# console_schematic_switches.net
KiCad netlist of a schematic drawn in Altium Designer
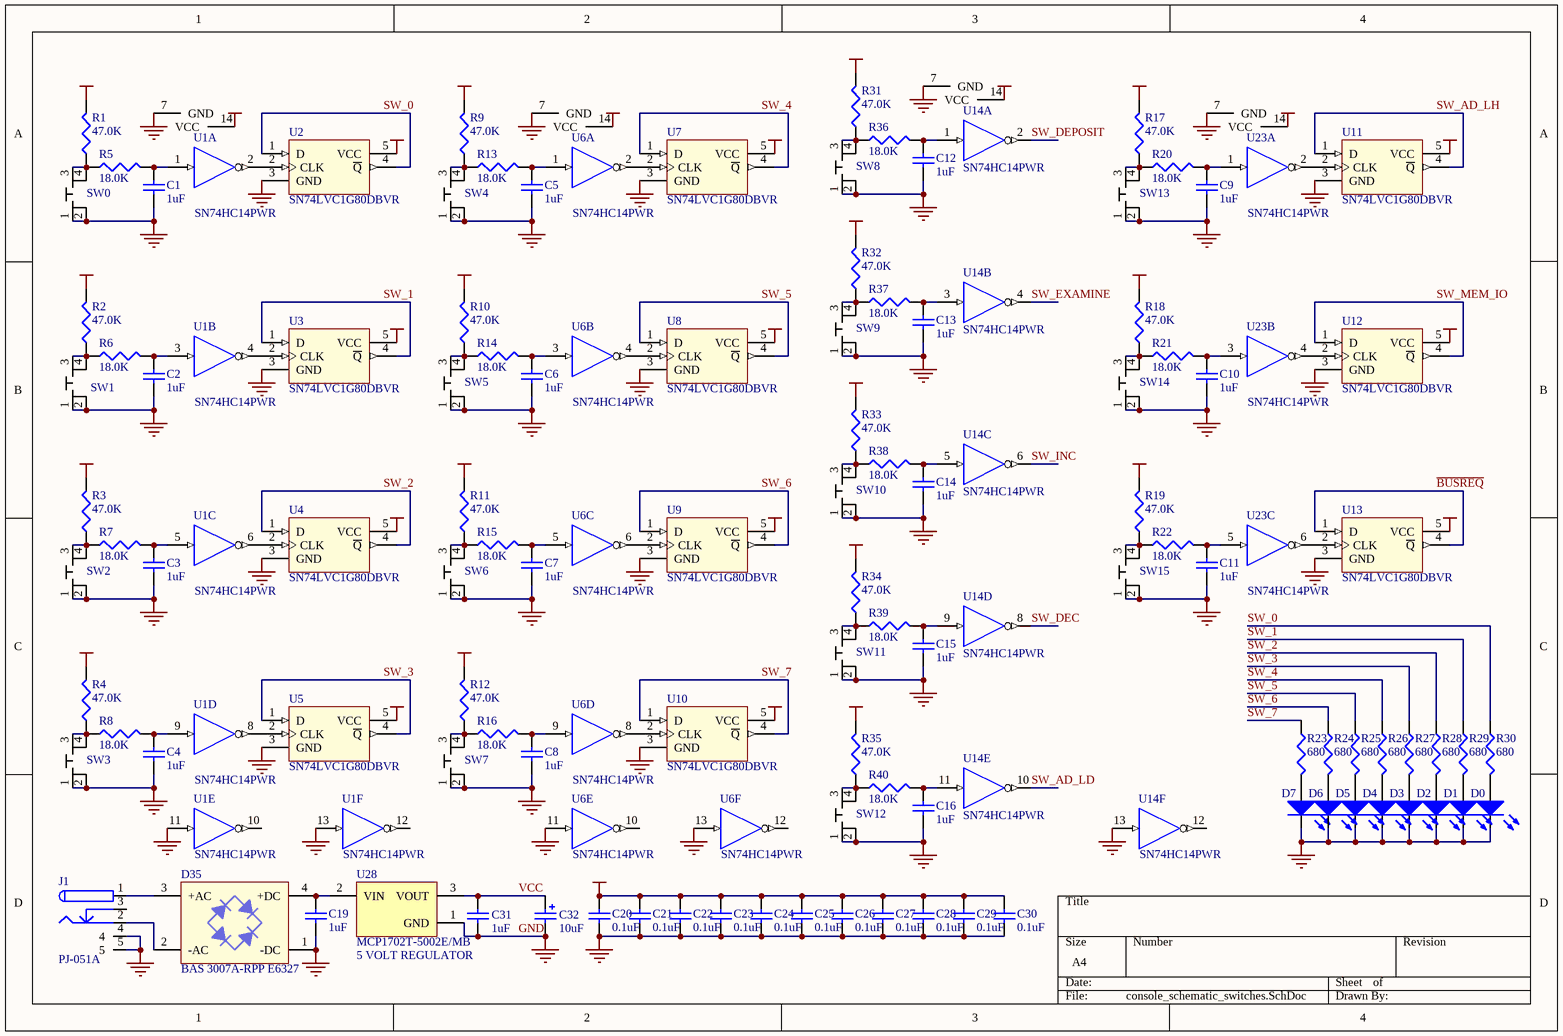
[diagram p0: console_schematic_switches.SchDoc]

(export (version "E")
  (design (tool "Eeschema 10.0.6"))
  (components
    (comp (ref "C1")
      (value "1uF")
      (footprint "smari_lib_pcb:0805")
      (description "CAP 1.0UF 16V CERAMIC X7R 0805")
      (libsource (lib "smari_lib_schematic") (part "C0805"))
    )
    (comp (ref "C2")
      (value "1uF")
      (footprint "smari_lib_pcb:0805")
      (description "CAP 1.0UF 16V CERAMIC X7R 0805")
      (libsource (lib "smari_lib_schematic") (part "C0805"))
    )
    (comp (ref "C3")
      (value "1uF")
      (footprint "smari_lib_pcb:0805")
      (description "CAP 1.0UF 16V CERAMIC X7R 0805")
      (libsource (lib "smari_lib_schematic") (part "C0805"))
    )
    (comp (ref "C4")
      (value "1uF")
      (footprint "smari_lib_pcb:0805")
      (description "CAP 1.0UF 16V CERAMIC X7R 0805")
      (libsource (lib "smari_lib_schematic") (part "C0805"))
    )
    (comp (ref "C5")
      (value "1uF")
      (footprint "smari_lib_pcb:0805")
      (description "CAP 1.0UF 16V CERAMIC X7R 0805")
      (libsource (lib "smari_lib_schematic") (part "C0805"))
    )
    (comp (ref "C6")
      (value "1uF")
      (footprint "smari_lib_pcb:0805")
      (description "CAP 1.0UF 16V CERAMIC X7R 0805")
      (libsource (lib "smari_lib_schematic") (part "C0805"))
    )
    (comp (ref "C7")
      (value "1uF")
      (footprint "smari_lib_pcb:0805")
      (description "CAP 1.0UF 16V CERAMIC X7R 0805")
      (libsource (lib "smari_lib_schematic") (part "C0805"))
    )
    (comp (ref "C8")
      (value "1uF")
      (footprint "smari_lib_pcb:0805")
      (description "CAP 1.0UF 16V CERAMIC X7R 0805")
      (libsource (lib "smari_lib_schematic") (part "C0805"))
    )
    (comp (ref "C9")
      (value "1uF")
      (footprint "smari_lib_pcb:0805")
      (description "CAP 1.0UF 16V CERAMIC X7R 0805")
      (libsource (lib "smari_lib_schematic") (part "C0805"))
    )
    (comp (ref "C10")
      (value "1uF")
      (footprint "smari_lib_pcb:0805")
      (description "CAP 1.0UF 16V CERAMIC X7R 0805")
      (libsource (lib "smari_lib_schematic") (part "C0805"))
    )
    (comp (ref "C11")
      (value "1uF")
      (footprint "smari_lib_pcb:0805")
      (description "CAP 1.0UF 16V CERAMIC X7R 0805")
      (libsource (lib "smari_lib_schematic") (part "C0805"))
    )
    (comp (ref "C12")
      (value "1uF")
      (footprint "smari_lib_pcb:0805")
      (description "CAP 1.0UF 16V CERAMIC X7R 0805")
      (libsource (lib "smari_lib_schematic") (part "C0805"))
    )
    (comp (ref "C13")
      (value "1uF")
      (footprint "smari_lib_pcb:0805")
      (description "CAP 1.0UF 16V CERAMIC X7R 0805")
      (libsource (lib "smari_lib_schematic") (part "C0805"))
    )
    (comp (ref "C14")
      (value "1uF")
      (footprint "smari_lib_pcb:0805")
      (description "CAP 1.0UF 16V CERAMIC X7R 0805")
      (libsource (lib "smari_lib_schematic") (part "C0805"))
    )
    (comp (ref "C15")
      (value "1uF")
      (footprint "smari_lib_pcb:0805")
      (description "CAP 1.0UF 16V CERAMIC X7R 0805")
      (libsource (lib "smari_lib_schematic") (part "C0805"))
    )
    (comp (ref "C16")
      (value "1uF")
      (footprint "smari_lib_pcb:0805")
      (description "CAP 1.0UF 16V CERAMIC X7R 0805")
      (libsource (lib "smari_lib_schematic") (part "C0805"))
    )
    (comp (ref "C19")
      (value "1uF")
      (footprint "smari_lib_pcb:0805")
      (description "CAP 1.0UF 16V CERAMIC X7R 0805")
      (libsource (lib "smari_lib_schematic") (part "C0805"))
    )
    (comp (ref "C20")
      (value "0.1uF")
      (footprint "smari_lib_pcb:0603")
      (description "CAP .10UF 16V CERAMIC X7R 0603")
      (libsource (lib "smari_lib_schematic") (part "C0603"))
    )
    (comp (ref "C21")
      (value "0.1uF")
      (footprint "smari_lib_pcb:0603")
      (description "CAP .10UF 16V CERAMIC X7R 0603")
      (libsource (lib "smari_lib_schematic") (part "C0603"))
    )
    (comp (ref "C22")
      (value "0.1uF")
      (footprint "smari_lib_pcb:0603")
      (description "CAP .10UF 16V CERAMIC X7R 0603")
      (libsource (lib "smari_lib_schematic") (part "C0603"))
    )
    (comp (ref "C23")
      (value "0.1uF")
      (footprint "smari_lib_pcb:0603")
      (description "CAP .10UF 16V CERAMIC X7R 0603")
      (libsource (lib "smari_lib_schematic") (part "C0603"))
    )
    (comp (ref "C24")
      (value "0.1uF")
      (footprint "smari_lib_pcb:0603")
      (description "CAP .10UF 16V CERAMIC X7R 0603")
      (libsource (lib "smari_lib_schematic") (part "C0603"))
    )
    (comp (ref "C25")
      (value "0.1uF")
      (footprint "smari_lib_pcb:0603")
      (description "CAP .10UF 16V CERAMIC X7R 0603")
      (libsource (lib "smari_lib_schematic") (part "C0603"))
    )
    (comp (ref "C26")
      (value "0.1uF")
      (footprint "smari_lib_pcb:0603")
      (description "CAP .10UF 16V CERAMIC X7R 0603")
      (libsource (lib "smari_lib_schematic") (part "C0603"))
    )
    (comp (ref "C27")
      (value "0.1uF")
      (footprint "smari_lib_pcb:0603")
      (description "CAP .10UF 16V CERAMIC X7R 0603")
      (libsource (lib "smari_lib_schematic") (part "C0603"))
    )
    (comp (ref "C28")
      (value "0.1uF")
      (footprint "smari_lib_pcb:0603")
      (description "CAP .10UF 16V CERAMIC X7R 0603")
      (libsource (lib "smari_lib_schematic") (part "C0603"))
    )
    (comp (ref "C29")
      (value "0.1uF")
      (footprint "smari_lib_pcb:0603")
      (description "CAP .10UF 16V CERAMIC X7R 0603")
      (libsource (lib "smari_lib_schematic") (part "C0603"))
    )
    (comp (ref "C30")
      (value "0.1uF")
      (footprint "smari_lib_pcb:0603")
      (description "CAP .10UF 16V CERAMIC X7R 0603")
      (libsource (lib "smari_lib_schematic") (part "C0603"))
    )
    (comp (ref "C31")
      (value "1uF")
      (footprint "smari_lib_pcb:0805")
      (description "CAP 1.0UF 16V CERAMIC X7R 0805")
      (libsource (lib "smari_lib_schematic") (part "C0805"))
    )
    (comp (ref "C32")
      (value "10uF")
      (footprint "smari_lib_pcb:1206_A")
      (description "CAPACITOR TANT 10UF 10V 10% SMD")
      (libsource (lib "smari_lib_schematic") (part "T491A"))
    )
    (comp (ref "D0")
      (value "LTST-C190KRKT")
      (footprint "smari_lib_pcb:APG1608")
      (description "LED SUPER RED CLEAR 0603 SMD")
      (libsource (lib "smari_lib_schematic") (part "LTST-C190KRKT"))
    )
    (comp (ref "D1")
      (value "LTST-C190KRKT")
      (footprint "smari_lib_pcb:APG1608")
      (description "LED SUPER RED CLEAR 0603 SMD")
      (libsource (lib "smari_lib_schematic") (part "LTST-C190KRKT"))
    )
    (comp (ref "D2")
      (value "LTST-C190KRKT")
      (footprint "smari_lib_pcb:APG1608")
      (description "LED SUPER RED CLEAR 0603 SMD")
      (libsource (lib "smari_lib_schematic") (part "LTST-C190KRKT"))
    )
    (comp (ref "D3")
      (value "LTST-C190KRKT")
      (footprint "smari_lib_pcb:APG1608")
      (description "LED SUPER RED CLEAR 0603 SMD")
      (libsource (lib "smari_lib_schematic") (part "LTST-C190KRKT"))
    )
    (comp (ref "D4")
      (value "LTST-C190KRKT")
      (footprint "smari_lib_pcb:APG1608")
      (description "LED SUPER RED CLEAR 0603 SMD")
      (libsource (lib "smari_lib_schematic") (part "LTST-C190KRKT"))
    )
    (comp (ref "D5")
      (value "LTST-C190KRKT")
      (footprint "smari_lib_pcb:APG1608")
      (description "LED SUPER RED CLEAR 0603 SMD")
      (libsource (lib "smari_lib_schematic") (part "LTST-C190KRKT"))
    )
    (comp (ref "D6")
      (value "LTST-C190KRKT")
      (footprint "smari_lib_pcb:APG1608")
      (description "LED SUPER RED CLEAR 0603 SMD")
      (libsource (lib "smari_lib_schematic") (part "LTST-C190KRKT"))
    )
    (comp (ref "D7")
      (value "LTST-C190KRKT")
      (footprint "smari_lib_pcb:APG1608")
      (description "LED SUPER RED CLEAR 0603 SMD")
      (libsource (lib "smari_lib_schematic") (part "LTST-C190KRKT"))
    )
    (comp (ref "D35")
      (value "BAS 3007A-RPP E6327")
      (footprint "smari_lib_pcb:SOT143")
      (description "DIODE SCHOTTKY 30V 900MA SOT143")
      (libsource (lib "smari_lib_schematic") (part "BAS 3007A-RPP E6327"))
    )
    (comp (ref "J1")
      (value "PJ-051A")
      (footprint "smari_lib_pcb:PJ-051A")
      (description "CON PWR JCK 2.0 X 6.0MM W/SHLD")
      (libsource (lib "smari_lib_schematic") (part "PJ-051A"))
    )
    (comp (ref "R1")
      (value "47.0K")
      (footprint "smari_lib_pcb:0603")
      (description "RES 47.0K OHM 1/10W 1% 0603 SMD")
      (libsource (lib "smari_lib_schematic") (part "MCR03EZPFX"))
    )
    (comp (ref "R2")
      (value "47.0K")
      (footprint "smari_lib_pcb:0603")
      (description "RES 47.0K OHM 1/10W 1% 0603 SMD")
      (libsource (lib "smari_lib_schematic") (part "MCR03EZPFX"))
    )
    (comp (ref "R3")
      (value "47.0K")
      (footprint "smari_lib_pcb:0603")
      (description "RES 47.0K OHM 1/10W 1% 0603 SMD")
      (libsource (lib "smari_lib_schematic") (part "MCR03EZPFX"))
    )
    (comp (ref "R4")
      (value "47.0K")
      (footprint "smari_lib_pcb:0603")
      (description "RES 47.0K OHM 1/10W 1% 0603 SMD")
      (libsource (lib "smari_lib_schematic") (part "MCR03EZPFX"))
    )
    (comp (ref "R5")
      (value "18.0K")
      (footprint "smari_lib_pcb:0603")
      (description "RES 18.0K OHM 1/10W 1% 0603 SMD")
      (libsource (lib "smari_lib_schematic") (part "MCR03EZPFX"))
    )
    (comp (ref "R6")
      (value "18.0K")
      (footprint "smari_lib_pcb:0603")
      (description "RES 18.0K OHM 1/10W 1% 0603 SMD")
      (libsource (lib "smari_lib_schematic") (part "MCR03EZPFX"))
    )
    (comp (ref "R7")
      (value "18.0K")
      (footprint "smari_lib_pcb:0603")
      (description "RES 18.0K OHM 1/10W 1% 0603 SMD")
      (libsource (lib "smari_lib_schematic") (part "MCR03EZPFX"))
    )
    (comp (ref "R8")
      (value "18.0K")
      (footprint "smari_lib_pcb:0603")
      (description "RES 18.0K OHM 1/10W 1% 0603 SMD")
      (libsource (lib "smari_lib_schematic") (part "MCR03EZPFX"))
    )
    (comp (ref "R9")
      (value "47.0K")
      (footprint "smari_lib_pcb:0603")
      (description "RES 47.0K OHM 1/10W 1% 0603 SMD")
      (libsource (lib "smari_lib_schematic") (part "MCR03EZPFX"))
    )
    (comp (ref "R10")
      (value "47.0K")
      (footprint "smari_lib_pcb:0603")
      (description "RES 47.0K OHM 1/10W 1% 0603 SMD")
      (libsource (lib "smari_lib_schematic") (part "MCR03EZPFX"))
    )
    (comp (ref "R11")
      (value "47.0K")
      (footprint "smari_lib_pcb:0603")
      (description "RES 47.0K OHM 1/10W 1% 0603 SMD")
      (libsource (lib "smari_lib_schematic") (part "MCR03EZPFX"))
    )
    (comp (ref "R12")
      (value "47.0K")
      (footprint "smari_lib_pcb:0603")
      (description "RES 47.0K OHM 1/10W 1% 0603 SMD")
      (libsource (lib "smari_lib_schematic") (part "MCR03EZPFX"))
    )
    (comp (ref "R13")
      (value "18.0K")
      (footprint "smari_lib_pcb:0603")
      (description "RES 18.0K OHM 1/10W 1% 0603 SMD")
      (libsource (lib "smari_lib_schematic") (part "MCR03EZPFX"))
    )
    (comp (ref "R14")
      (value "18.0K")
      (footprint "smari_lib_pcb:0603")
      (description "RES 18.0K OHM 1/10W 1% 0603 SMD")
      (libsource (lib "smari_lib_schematic") (part "MCR03EZPFX"))
    )
    (comp (ref "R15")
      (value "18.0K")
      (footprint "smari_lib_pcb:0603")
      (description "RES 18.0K OHM 1/10W 1% 0603 SMD")
      (libsource (lib "smari_lib_schematic") (part "MCR03EZPFX"))
    )
    (comp (ref "R16")
      (value "18.0K")
      (footprint "smari_lib_pcb:0603")
      (description "RES 18.0K OHM 1/10W 1% 0603 SMD")
      (libsource (lib "smari_lib_schematic") (part "MCR03EZPFX"))
    )
    (comp (ref "R17")
      (value "47.0K")
      (footprint "smari_lib_pcb:0603")
      (description "RES 47.0K OHM 1/10W 1% 0603 SMD")
      (libsource (lib "smari_lib_schematic") (part "MCR03EZPFX"))
    )
    (comp (ref "R18")
      (value "47.0K")
      (footprint "smari_lib_pcb:0603")
      (description "RES 47.0K OHM 1/10W 1% 0603 SMD")
      (libsource (lib "smari_lib_schematic") (part "MCR03EZPFX"))
    )
    (comp (ref "R19")
      (value "47.0K")
      (footprint "smari_lib_pcb:0603")
      (description "RES 47.0K OHM 1/10W 1% 0603 SMD")
      (libsource (lib "smari_lib_schematic") (part "MCR03EZPFX"))
    )
    (comp (ref "R20")
      (value "18.0K")
      (footprint "smari_lib_pcb:0603")
      (description "RES 18.0K OHM 1/10W 1% 0603 SMD")
      (libsource (lib "smari_lib_schematic") (part "MCR03EZPFX"))
    )
    (comp (ref "R21")
      (value "18.0K")
      (footprint "smari_lib_pcb:0603")
      (description "RES 18.0K OHM 1/10W 1% 0603 SMD")
      (libsource (lib "smari_lib_schematic") (part "MCR03EZPFX"))
    )
    (comp (ref "R22")
      (value "18.0K")
      (footprint "smari_lib_pcb:0603")
      (description "RES 18.0K OHM 1/10W 1% 0603 SMD")
      (libsource (lib "smari_lib_schematic") (part "MCR03EZPFX"))
    )
    (comp (ref "R23")
      (value "680")
      (footprint "smari_lib_pcb:0603")
      (description "RES 680 OHM 1/10W 1% 0603 SMD")
      (libsource (lib "smari_lib_schematic") (part "MCR03EZPFX"))
    )
    (comp (ref "R24")
      (value "680")
      (footprint "smari_lib_pcb:0603")
      (description "RES 680 OHM 1/10W 1% 0603 SMD")
      (libsource (lib "smari_lib_schematic") (part "MCR03EZPFX"))
    )
    (comp (ref "R25")
      (value "680")
      (footprint "smari_lib_pcb:0603")
      (description "RES 680 OHM 1/10W 1% 0603 SMD")
      (libsource (lib "smari_lib_schematic") (part "MCR03EZPFX"))
    )
    (comp (ref "R26")
      (value "680")
      (footprint "smari_lib_pcb:0603")
      (description "RES 680 OHM 1/10W 1% 0603 SMD")
      (libsource (lib "smari_lib_schematic") (part "MCR03EZPFX"))
    )
    (comp (ref "R27")
      (value "680")
      (footprint "smari_lib_pcb:0603")
      (description "RES 680 OHM 1/10W 1% 0603 SMD")
      (libsource (lib "smari_lib_schematic") (part "MCR03EZPFX"))
    )
    (comp (ref "R28")
      (value "680")
      (footprint "smari_lib_pcb:0603")
      (description "RES 680 OHM 1/10W 1% 0603 SMD")
      (libsource (lib "smari_lib_schematic") (part "MCR03EZPFX"))
    )
    (comp (ref "R29")
      (value "680")
      (footprint "smari_lib_pcb:0603")
      (description "RES 680 OHM 1/10W 1% 0603 SMD")
      (libsource (lib "smari_lib_schematic") (part "MCR03EZPFX"))
    )
    (comp (ref "R30")
      (value "680")
      (footprint "smari_lib_pcb:0603")
      (description "RES 680 OHM 1/10W 1% 0603 SMD")
      (libsource (lib "smari_lib_schematic") (part "MCR03EZPFX"))
    )
    (comp (ref "R31")
      (value "47.0K")
      (footprint "smari_lib_pcb:0603")
      (description "RES 47.0K OHM 1/10W 1% 0603 SMD")
      (libsource (lib "smari_lib_schematic") (part "MCR03EZPFX"))
    )
    (comp (ref "R32")
      (value "47.0K")
      (footprint "smari_lib_pcb:0603")
      (description "RES 47.0K OHM 1/10W 1% 0603 SMD")
      (libsource (lib "smari_lib_schematic") (part "MCR03EZPFX"))
    )
    (comp (ref "R33")
      (value "47.0K")
      (footprint "smari_lib_pcb:0603")
      (description "RES 47.0K OHM 1/10W 1% 0603 SMD")
      (libsource (lib "smari_lib_schematic") (part "MCR03EZPFX"))
    )
    (comp (ref "R34")
      (value "47.0K")
      (footprint "smari_lib_pcb:0603")
      (description "RES 47.0K OHM 1/10W 1% 0603 SMD")
      (libsource (lib "smari_lib_schematic") (part "MCR03EZPFX"))
    )
    (comp (ref "R35")
      (value "47.0K")
      (footprint "smari_lib_pcb:0603")
      (description "RES 47.0K OHM 1/10W 1% 0603 SMD")
      (libsource (lib "smari_lib_schematic") (part "MCR03EZPFX"))
    )
    (comp (ref "R36")
      (value "18.0K")
      (footprint "smari_lib_pcb:0603")
      (description "RES 18.0K OHM 1/10W 1% 0603 SMD")
      (libsource (lib "smari_lib_schematic") (part "MCR03EZPFX"))
    )
    (comp (ref "R37")
      (value "18.0K")
      (footprint "smari_lib_pcb:0603")
      (description "RES 18.0K OHM 1/10W 1% 0603 SMD")
      (libsource (lib "smari_lib_schematic") (part "MCR03EZPFX"))
    )
    (comp (ref "R38")
      (value "18.0K")
      (footprint "smari_lib_pcb:0603")
      (description "RES 18.0K OHM 1/10W 1% 0603 SMD")
      (libsource (lib "smari_lib_schematic") (part "MCR03EZPFX"))
    )
    (comp (ref "R39")
      (value "18.0K")
      (footprint "smari_lib_pcb:0603")
      (description "RES 18.0K OHM 1/10W 1% 0603 SMD")
      (libsource (lib "smari_lib_schematic") (part "MCR03EZPFX"))
    )
    (comp (ref "R40")
      (value "18.0K")
      (footprint "smari_lib_pcb:0603")
      (description "RES 18.0K OHM 1/10W 1% 0603 SMD")
      (libsource (lib "smari_lib_schematic") (part "MCR03EZPFX"))
    )
    (comp (ref "SW0")
      (value "PTS645SM43SMTR LFS")
      (footprint "smari_lib_pcb:PTS645SM43SMTR LFS")
      (description "SWITCH TACT 6MM 160GF H=4.3MM")
      (libsource (lib "smari_lib_schematic") (part "PTS645SM43SMTR LFS"))
    )
    (comp (ref "SW1")
      (value "PTS645SM43SMTR LFS")
      (footprint "smari_lib_pcb:PTS645SM43SMTR LFS")
      (description "SWITCH TACT 6MM 160GF H=4.3MM")
      (libsource (lib "smari_lib_schematic") (part "PTS645SM43SMTR LFS"))
    )
    (comp (ref "SW2")
      (value "PTS645SM43SMTR LFS")
      (footprint "smari_lib_pcb:PTS645SM43SMTR LFS")
      (description "SWITCH TACT 6MM 160GF H=4.3MM")
      (libsource (lib "smari_lib_schematic") (part "PTS645SM43SMTR LFS"))
    )
    (comp (ref "SW3")
      (value "PTS645SM43SMTR LFS")
      (footprint "smari_lib_pcb:PTS645SM43SMTR LFS")
      (description "SWITCH TACT 6MM 160GF H=4.3MM")
      (libsource (lib "smari_lib_schematic") (part "PTS645SM43SMTR LFS"))
    )
    (comp (ref "SW4")
      (value "PTS645SM43SMTR LFS")
      (footprint "smari_lib_pcb:PTS645SM43SMTR LFS")
      (description "SWITCH TACT 6MM 160GF H=4.3MM")
      (libsource (lib "smari_lib_schematic") (part "PTS645SM43SMTR LFS"))
    )
    (comp (ref "SW5")
      (value "PTS645SM43SMTR LFS")
      (footprint "smari_lib_pcb:PTS645SM43SMTR LFS")
      (description "SWITCH TACT 6MM 160GF H=4.3MM")
      (libsource (lib "smari_lib_schematic") (part "PTS645SM43SMTR LFS"))
    )
    (comp (ref "SW6")
      (value "PTS645SM43SMTR LFS")
      (footprint "smari_lib_pcb:PTS645SM43SMTR LFS")
      (description "SWITCH TACT 6MM 160GF H=4.3MM")
      (libsource (lib "smari_lib_schematic") (part "PTS645SM43SMTR LFS"))
    )
    (comp (ref "SW7")
      (value "PTS645SM43SMTR LFS")
      (footprint "smari_lib_pcb:PTS645SM43SMTR LFS")
      (description "SWITCH TACT 6MM 160GF H=4.3MM")
      (libsource (lib "smari_lib_schematic") (part "PTS645SM43SMTR LFS"))
    )
    (comp (ref "SW8")
      (value "PTS645SM43SMTR LFS")
      (footprint "smari_lib_pcb:PTS645SM43SMTR LFS")
      (description "SWITCH TACT 6MM 160GF H=4.3MM")
      (libsource (lib "smari_lib_schematic") (part "PTS645SM43SMTR LFS"))
    )
    (comp (ref "SW9")
      (value "PTS645SM43SMTR LFS")
      (footprint "smari_lib_pcb:PTS645SM43SMTR LFS")
      (description "SWITCH TACT 6MM 160GF H=4.3MM")
      (libsource (lib "smari_lib_schematic") (part "PTS645SM43SMTR LFS"))
    )
    (comp (ref "SW10")
      (value "PTS645SM43SMTR LFS")
      (footprint "smari_lib_pcb:PTS645SM43SMTR LFS")
      (description "SWITCH TACT 6MM 160GF H=4.3MM")
      (libsource (lib "smari_lib_schematic") (part "PTS645SM43SMTR LFS"))
    )
    (comp (ref "SW11")
      (value "PTS645SM43SMTR LFS")
      (footprint "smari_lib_pcb:PTS645SM43SMTR LFS")
      (description "SWITCH TACT 6MM 160GF H=4.3MM")
      (libsource (lib "smari_lib_schematic") (part "PTS645SM43SMTR LFS"))
    )
    (comp (ref "SW12")
      (value "PTS645SM43SMTR LFS")
      (footprint "smari_lib_pcb:PTS645SM43SMTR LFS")
      (description "SWITCH TACT 6MM 160GF H=4.3MM")
      (libsource (lib "smari_lib_schematic") (part "PTS645SM43SMTR LFS"))
    )
    (comp (ref "SW13")
      (value "PTS645SM43SMTR LFS")
      (footprint "smari_lib_pcb:PTS645SM43SMTR LFS")
      (description "SWITCH TACT 6MM 160GF H=4.3MM")
      (libsource (lib "smari_lib_schematic") (part "PTS645SM43SMTR LFS"))
    )
    (comp (ref "SW14")
      (value "PTS645SM43SMTR LFS")
      (footprint "smari_lib_pcb:PTS645SM43SMTR LFS")
      (description "SWITCH TACT 6MM 160GF H=4.3MM")
      (libsource (lib "smari_lib_schematic") (part "PTS645SM43SMTR LFS"))
    )
    (comp (ref "SW15")
      (value "PTS645SM43SMTR LFS")
      (footprint "smari_lib_pcb:PTS645SM43SMTR LFS")
      (description "SWITCH TACT 6MM 160GF H=4.3MM")
      (libsource (lib "smari_lib_schematic") (part "PTS645SM43SMTR LFS"))
    )
    (comp (ref "U1")
      (value "SN74HC14PWR")
      (footprint "smari_lib_pcb:PW014")
      (description "IC HEX SCHMITT-TRIG INV 14-TSSOP")
      (libsource (lib "smari_lib_schematic") (part "SN74HC14PWR"))
    )
    (comp (ref "U2")
      (value "SN74LVC1G80DBVR")
      (footprint "smari_lib_pcb:SOT-23-5 DBV R-PDSO-G5")
      (description "IC POSITIVE D-TYPE F-F SOT-23-5")
      (libsource (lib "smari_lib_schematic") (part "SN74LVC1G80DBVR"))
    )
    (comp (ref "U3")
      (value "SN74LVC1G80DBVR")
      (footprint "smari_lib_pcb:SOT-23-5 DBV R-PDSO-G5")
      (description "IC POSITIVE D-TYPE F-F SOT-23-5")
      (libsource (lib "smari_lib_schematic") (part "SN74LVC1G80DBVR"))
    )
    (comp (ref "U4")
      (value "SN74LVC1G80DBVR")
      (footprint "smari_lib_pcb:SOT-23-5 DBV R-PDSO-G5")
      (description "IC POSITIVE D-TYPE F-F SOT-23-5")
      (libsource (lib "smari_lib_schematic") (part "SN74LVC1G80DBVR"))
    )
    (comp (ref "U5")
      (value "SN74LVC1G80DBVR")
      (footprint "smari_lib_pcb:SOT-23-5 DBV R-PDSO-G5")
      (description "IC POSITIVE D-TYPE F-F SOT-23-5")
      (libsource (lib "smari_lib_schematic") (part "SN74LVC1G80DBVR"))
    )
    (comp (ref "U6")
      (value "SN74HC14PWR")
      (footprint "smari_lib_pcb:PW014")
      (description "IC HEX SCHMITT-TRIG INV 14-TSSOP")
      (libsource (lib "smari_lib_schematic") (part "SN74HC14PWR"))
    )
    (comp (ref "U7")
      (value "SN74LVC1G80DBVR")
      (footprint "smari_lib_pcb:SOT-23-5 DBV R-PDSO-G5")
      (description "IC POSITIVE D-TYPE F-F SOT-23-5")
      (libsource (lib "smari_lib_schematic") (part "SN74LVC1G80DBVR"))
    )
    (comp (ref "U8")
      (value "SN74LVC1G80DBVR")
      (footprint "smari_lib_pcb:SOT-23-5 DBV R-PDSO-G5")
      (description "IC POSITIVE D-TYPE F-F SOT-23-5")
      (libsource (lib "smari_lib_schematic") (part "SN74LVC1G80DBVR"))
    )
    (comp (ref "U9")
      (value "SN74LVC1G80DBVR")
      (footprint "smari_lib_pcb:SOT-23-5 DBV R-PDSO-G5")
      (description "IC POSITIVE D-TYPE F-F SOT-23-5")
      (libsource (lib "smari_lib_schematic") (part "SN74LVC1G80DBVR"))
    )
    (comp (ref "U10")
      (value "SN74LVC1G80DBVR")
      (footprint "smari_lib_pcb:SOT-23-5 DBV R-PDSO-G5")
      (description "IC POSITIVE D-TYPE F-F SOT-23-5")
      (libsource (lib "smari_lib_schematic") (part "SN74LVC1G80DBVR"))
    )
    (comp (ref "U11")
      (value "SN74LVC1G80DBVR")
      (footprint "smari_lib_pcb:SOT-23-5 DBV R-PDSO-G5")
      (description "IC POSITIVE D-TYPE F-F SOT-23-5")
      (libsource (lib "smari_lib_schematic") (part "SN74LVC1G80DBVR"))
    )
    (comp (ref "U12")
      (value "SN74LVC1G80DBVR")
      (footprint "smari_lib_pcb:SOT-23-5 DBV R-PDSO-G5")
      (description "IC POSITIVE D-TYPE F-F SOT-23-5")
      (libsource (lib "smari_lib_schematic") (part "SN74LVC1G80DBVR"))
    )
    (comp (ref "U13")
      (value "SN74LVC1G80DBVR")
      (footprint "smari_lib_pcb:SOT-23-5 DBV R-PDSO-G5")
      (description "IC POSITIVE D-TYPE F-F SOT-23-5")
      (libsource (lib "smari_lib_schematic") (part "SN74LVC1G80DBVR"))
    )
    (comp (ref "U14")
      (value "SN74HC14PWR")
      (footprint "smari_lib_pcb:PW014")
      (description "IC HEX SCHMITT-TRIG INV 14-TSSOP")
      (libsource (lib "") (part "SN74HC14PWR_2"))
    )
    (comp (ref "U23")
      (value "SN74HC14PWR")
      (footprint "smari_lib_pcb:PW014")
      (description "IC HEX SCHMITT-TRIG INV 14-TSSOP")
      (libsource (lib "smari_lib_schematic") (part "SN74HC14PWR"))
    )
    (comp (ref "U28")
      (value "MCP1702T-5002E/MB")
      (footprint "smari_lib_pcb:SOT-89")
      (description "IC REG LDO 5V 250MA SOT-89-3")
      (fields (field (name "NOTES") "5 VOLT REGULATOR"))
      (libsource (lib "smari_lib_schematic") (part "MCP1702T-5002E/MB"))
    )
  )
  (nets
    (net (code "1") (name "/SW_0") (class "Default")
      (node (ref "R30") (pin "1") (pinfunction "1_1") (pintype "passive"))
      (node (ref "U2") (pin "1") (pinfunction "D_1") (pintype "input"))
      (node (ref "U2") (pin "4") (pinfunction "~{Q}_4") (pintype "output"))
    )
    (net (code "2") (name "/SW_1") (class "Default")
      (node (ref "R29") (pin "1") (pinfunction "1_1") (pintype "passive"))
      (node (ref "U3") (pin "1") (pinfunction "D_1") (pintype "input"))
      (node (ref "U3") (pin "4") (pinfunction "~{Q}_4") (pintype "output"))
    )
    (net (code "3") (name "/SW_2") (class "Default")
      (node (ref "R28") (pin "1") (pinfunction "1_1") (pintype "passive"))
      (node (ref "U4") (pin "1") (pinfunction "D_1") (pintype "input"))
      (node (ref "U4") (pin "4") (pinfunction "~{Q}_4") (pintype "output"))
    )
    (net (code "4") (name "/SW_3") (class "Default")
      (node (ref "R27") (pin "1") (pinfunction "1_1") (pintype "passive"))
      (node (ref "U5") (pin "1") (pinfunction "D_1") (pintype "input"))
      (node (ref "U5") (pin "4") (pinfunction "~{Q}_4") (pintype "output"))
    )
    (net (code "5") (name "/SW_4") (class "Default")
      (node (ref "R26") (pin "1") (pinfunction "1_1") (pintype "passive"))
      (node (ref "U7") (pin "1") (pinfunction "D_1") (pintype "input"))
      (node (ref "U7") (pin "4") (pinfunction "~{Q}_4") (pintype "output"))
    )
    (net (code "6") (name "/SW_5") (class "Default")
      (node (ref "R25") (pin "1") (pinfunction "1_1") (pintype "passive"))
      (node (ref "U8") (pin "1") (pinfunction "D_1") (pintype "input"))
      (node (ref "U8") (pin "4") (pinfunction "~{Q}_4") (pintype "output"))
    )
    (net (code "7") (name "/SW_6") (class "Default")
      (node (ref "R24") (pin "1") (pinfunction "1_1") (pintype "passive"))
      (node (ref "U9") (pin "1") (pinfunction "D_1") (pintype "input"))
      (node (ref "U9") (pin "4") (pinfunction "~{Q}_4") (pintype "output"))
    )
    (net (code "8") (name "/SW_7") (class "Default")
      (node (ref "R23") (pin "1") (pinfunction "1_1") (pintype "passive"))
      (node (ref "U10") (pin "1") (pinfunction "D_1") (pintype "input"))
      (node (ref "U10") (pin "4") (pinfunction "~{Q}_4") (pintype "output"))
    )
    (net (code "9") (name "/SW_AD_LD") (class "Default")
      (node (ref "U14") (pin "10") (pinfunction "Y_10") (pintype "output"))
    )
    (net (code "10") (name "/SW_AD_LH") (class "Default")
      (node (ref "U11") (pin "1") (pinfunction "D_1") (pintype "input"))
      (node (ref "U11") (pin "4") (pinfunction "~{Q}_4") (pintype "output"))
    )
    (net (code "11") (name "/SW_DEC") (class "Default")
      (node (ref "U14") (pin "8") (pinfunction "Y_8") (pintype "output"))
    )
    (net (code "12") (name "/SW_DEPOSIT") (class "Default")
      (node (ref "U14") (pin "2") (pinfunction "Y_2") (pintype "output"))
    )
    (net (code "13") (name "/SW_EXAMINE") (class "Default")
      (node (ref "U14") (pin "4") (pinfunction "Y_4") (pintype "output"))
    )
    (net (code "14") (name "/SW_INC") (class "Default")
      (node (ref "U14") (pin "6") (pinfunction "Y_6") (pintype "output"))
    )
    (net (code "15") (name "/SW_MEM_IO") (class "Default")
      (node (ref "U12") (pin "1") (pinfunction "D_1") (pintype "input"))
      (node (ref "U12") (pin "4") (pinfunction "~{Q}_4") (pintype "output"))
    )
    (net (code "16") (name "/~{BUSREQ}") (class "Default")
      (node (ref "U13") (pin "1") (pinfunction "D_1") (pintype "input"))
      (node (ref "U13") (pin "4") (pinfunction "~{Q}_4") (pintype "output"))
    )
    (net (code "17") (name "GND") (class "Default")
      (node (ref "C1") (pin "1") (pinfunction "1_1") (pintype "passive"))
      (node (ref "C10") (pin "1") (pinfunction "1_1") (pintype "passive"))
      (node (ref "C11") (pin "1") (pinfunction "1_1") (pintype "passive"))
      (node (ref "C12") (pin "1") (pinfunction "1_1") (pintype "passive"))
      (node (ref "C13") (pin "1") (pinfunction "1_1") (pintype "passive"))
      (node (ref "C14") (pin "1") (pinfunction "1_1") (pintype "passive"))
      (node (ref "C15") (pin "1") (pinfunction "1_1") (pintype "passive"))
      (node (ref "C16") (pin "1") (pinfunction "1_1") (pintype "passive"))
      (node (ref "C19") (pin "2") (pinfunction "2_2") (pintype "passive"))
      (node (ref "C2") (pin "1") (pinfunction "1_1") (pintype "passive"))
      (node (ref "C20") (pin "1") (pinfunction "1_1") (pintype "passive"))
      (node (ref "C21") (pin "1") (pinfunction "1_1") (pintype "passive"))
      (node (ref "C22") (pin "1") (pinfunction "1_1") (pintype "passive"))
      (node (ref "C23") (pin "1") (pinfunction "1_1") (pintype "passive"))
      (node (ref "C24") (pin "1") (pinfunction "1_1") (pintype "passive"))
      (node (ref "C25") (pin "1") (pinfunction "1_1") (pintype "passive"))
      (node (ref "C26") (pin "1") (pinfunction "1_1") (pintype "passive"))
      (node (ref "C27") (pin "1") (pinfunction "1_1") (pintype "passive"))
      (node (ref "C28") (pin "1") (pinfunction "1_1") (pintype "passive"))
      (node (ref "C29") (pin "1") (pinfunction "1_1") (pintype "passive"))
      (node (ref "C3") (pin "1") (pinfunction "1_1") (pintype "passive"))
      (node (ref "C30") (pin "1") (pinfunction "1_1") (pintype "passive"))
      (node (ref "C31") (pin "2") (pinfunction "2_2") (pintype "passive"))
      (node (ref "C32") (pin "2") (pinfunction "2_2") (pintype "passive"))
      (node (ref "C4") (pin "1") (pinfunction "1_1") (pintype "passive"))
      (node (ref "C5") (pin "1") (pinfunction "1_1") (pintype "passive"))
      (node (ref "C6") (pin "1") (pinfunction "1_1") (pintype "passive"))
      (node (ref "C7") (pin "1") (pinfunction "1_1") (pintype "passive"))
      (node (ref "C8") (pin "1") (pinfunction "1_1") (pintype "passive"))
      (node (ref "C9") (pin "1") (pinfunction "1_1") (pintype "passive"))
      (node (ref "D0") (pin "2") (pinfunction "K_2") (pintype "passive"))
      (node (ref "D1") (pin "2") (pinfunction "K_2") (pintype "passive"))
      (node (ref "D2") (pin "2") (pinfunction "K_2") (pintype "passive"))
      (node (ref "D3") (pin "2") (pinfunction "K_2") (pintype "passive"))
      (node (ref "D35") (pin "1") (pinfunction "-DC_1") (pintype "power_in"))
      (node (ref "D4") (pin "2") (pinfunction "K_2") (pintype "passive"))
      (node (ref "D5") (pin "2") (pinfunction "K_2") (pintype "passive"))
      (node (ref "D6") (pin "2") (pinfunction "K_2") (pintype "passive"))
      (node (ref "D7") (pin "2") (pinfunction "K_2") (pintype "passive"))
      (node (ref "J1") (pin "4") (pinfunction "4_4") (pintype "passive"))
      (node (ref "J1") (pin "5") (pinfunction "5_5") (pintype "passive"))
      (node (ref "SW0") (pin "1") (pinfunction "1_1") (pintype "passive"))
      (node (ref "SW0") (pin "2") (pinfunction "2_2") (pintype "passive"))
      (node (ref "SW1") (pin "1") (pinfunction "1_1") (pintype "passive"))
      (node (ref "SW1") (pin "2") (pinfunction "2_2") (pintype "passive"))
      (node (ref "SW10") (pin "1") (pinfunction "1_1") (pintype "passive"))
      (node (ref "SW10") (pin "2") (pinfunction "2_2") (pintype "passive"))
      (node (ref "SW11") (pin "1") (pinfunction "1_1") (pintype "passive"))
      (node (ref "SW11") (pin "2") (pinfunction "2_2") (pintype "passive"))
      (node (ref "SW12") (pin "1") (pinfunction "1_1") (pintype "passive"))
      (node (ref "SW12") (pin "2") (pinfunction "2_2") (pintype "passive"))
      (node (ref "SW13") (pin "1") (pinfunction "1_1") (pintype "passive"))
      (node (ref "SW13") (pin "2") (pinfunction "2_2") (pintype "passive"))
      (node (ref "SW14") (pin "1") (pinfunction "1_1") (pintype "passive"))
      (node (ref "SW14") (pin "2") (pinfunction "2_2") (pintype "passive"))
      (node (ref "SW15") (pin "1") (pinfunction "1_1") (pintype "passive"))
      (node (ref "SW15") (pin "2") (pinfunction "2_2") (pintype "passive"))
      (node (ref "SW2") (pin "1") (pinfunction "1_1") (pintype "passive"))
      (node (ref "SW2") (pin "2") (pinfunction "2_2") (pintype "passive"))
      (node (ref "SW3") (pin "1") (pinfunction "1_1") (pintype "passive"))
      (node (ref "SW3") (pin "2") (pinfunction "2_2") (pintype "passive"))
      (node (ref "SW4") (pin "1") (pinfunction "1_1") (pintype "passive"))
      (node (ref "SW4") (pin "2") (pinfunction "2_2") (pintype "passive"))
      (node (ref "SW5") (pin "1") (pinfunction "1_1") (pintype "passive"))
      (node (ref "SW5") (pin "2") (pinfunction "2_2") (pintype "passive"))
      (node (ref "SW6") (pin "1") (pinfunction "1_1") (pintype "passive"))
      (node (ref "SW6") (pin "2") (pinfunction "2_2") (pintype "passive"))
      (node (ref "SW7") (pin "1") (pinfunction "1_1") (pintype "passive"))
      (node (ref "SW7") (pin "2") (pinfunction "2_2") (pintype "passive"))
      (node (ref "SW8") (pin "1") (pinfunction "1_1") (pintype "passive"))
      (node (ref "SW8") (pin "2") (pinfunction "2_2") (pintype "passive"))
      (node (ref "SW9") (pin "1") (pinfunction "1_1") (pintype "passive"))
      (node (ref "SW9") (pin "2") (pinfunction "2_2") (pintype "passive"))
      (node (ref "U1") (pin "11") (pinfunction "A_11") (pintype "input"))
      (node (ref "U1") (pin "13") (pinfunction "A_13") (pintype "input"))
      (node (ref "U1") (pin "7") (pinfunction "GND_7") (pintype "power_in"))
      (node (ref "U10") (pin "3") (pinfunction "GND_3") (pintype "power_in"))
      (node (ref "U11") (pin "3") (pinfunction "GND_3") (pintype "power_in"))
      (node (ref "U12") (pin "3") (pinfunction "GND_3") (pintype "power_in"))
      (node (ref "U13") (pin "3") (pinfunction "GND_3") (pintype "power_in"))
      (node (ref "U14") (pin "13") (pinfunction "A_13") (pintype "input"))
      (node (ref "U14") (pin "7") (pinfunction "GND_7") (pintype "power_in"))
      (node (ref "U2") (pin "3") (pinfunction "GND_3") (pintype "power_in"))
      (node (ref "U23") (pin "7") (pinfunction "GND_7") (pintype "power_in"))
      (node (ref "U28") (pin "1") (pinfunction "GND_1") (pintype "power_in"))
      (node (ref "U3") (pin "3") (pinfunction "GND_3") (pintype "power_in"))
      (node (ref "U4") (pin "3") (pinfunction "GND_3") (pintype "power_in"))
      (node (ref "U5") (pin "3") (pinfunction "GND_3") (pintype "power_in"))
      (node (ref "U6") (pin "11") (pinfunction "A_11") (pintype "input"))
      (node (ref "U6") (pin "13") (pinfunction "A_13") (pintype "input"))
      (node (ref "U6") (pin "7") (pinfunction "GND_7") (pintype "power_in"))
      (node (ref "U7") (pin "3") (pinfunction "GND_3") (pintype "power_in"))
      (node (ref "U8") (pin "3") (pinfunction "GND_3") (pintype "power_in"))
      (node (ref "U9") (pin "3") (pinfunction "GND_3") (pintype "power_in"))
    )
    (net (code "18") (name "Net-(D0-A)") (class "Default")
      (node (ref "D0") (pin "1") (pinfunction "A_1") (pintype "passive"))
      (node (ref "R30") (pin "2") (pinfunction "2_2") (pintype "passive"))
    )
    (net (code "19") (name "Net-(D1-A)") (class "Default")
      (node (ref "D1") (pin "1") (pinfunction "A_1") (pintype "passive"))
      (node (ref "R29") (pin "2") (pinfunction "2_2") (pintype "passive"))
    )
    (net (code "20") (name "Net-(D2-A)") (class "Default")
      (node (ref "D2") (pin "1") (pinfunction "A_1") (pintype "passive"))
      (node (ref "R28") (pin "2") (pinfunction "2_2") (pintype "passive"))
    )
    (net (code "21") (name "Net-(D3-A)") (class "Default")
      (node (ref "D3") (pin "1") (pinfunction "A_1") (pintype "passive"))
      (node (ref "R27") (pin "2") (pinfunction "2_2") (pintype "passive"))
    )
    (net (code "22") (name "Net-(D4-A)") (class "Default")
      (node (ref "D4") (pin "1") (pinfunction "A_1") (pintype "passive"))
      (node (ref "R26") (pin "2") (pinfunction "2_2") (pintype "passive"))
    )
    (net (code "23") (name "Net-(D5-A)") (class "Default")
      (node (ref "D5") (pin "1") (pinfunction "A_1") (pintype "passive"))
      (node (ref "R25") (pin "2") (pinfunction "2_2") (pintype "passive"))
    )
    (net (code "24") (name "Net-(D6-A)") (class "Default")
      (node (ref "D6") (pin "1") (pinfunction "A_1") (pintype "passive"))
      (node (ref "R24") (pin "2") (pinfunction "2_2") (pintype "passive"))
    )
    (net (code "25") (name "Net-(D7-A)") (class "Default")
      (node (ref "D7") (pin "1") (pinfunction "A_1") (pintype "passive"))
      (node (ref "R23") (pin "2") (pinfunction "2_2") (pintype "passive"))
    )
    (net (code "26") (name "Net-(D35-+AC)") (class "Default")
      (node (ref "D35") (pin "3") (pinfunction "+AC_3") (pintype "power_in"))
      (node (ref "J1") (pin "1") (pinfunction "1_1") (pintype "power_in"))
    )
    (net (code "27") (name "Net-(D35-+DC)") (class "Default")
      (node (ref "C19") (pin "1") (pinfunction "1_1") (pintype "passive"))
      (node (ref "D35") (pin "4") (pinfunction "+DC_4") (pintype "power_in"))
      (node (ref "U28") (pin "2") (pinfunction "VIN_2") (pintype "power_in"))
    )
    (net (code "28") (name "Net-(D35--AC)") (class "Default")
      (node (ref "D35") (pin "2") (pinfunction "-AC_2") (pintype "power_in"))
      (node (ref "J1") (pin "2") (pinfunction "2_2") (pintype "power_in"))
    )
    (net (code "29") (name "Net-(R1-Pad1)") (class "Default")
      (node (ref "R1") (pin "1") (pinfunction "1_1") (pintype "passive"))
      (node (ref "R5") (pin "1") (pinfunction "1_1") (pintype "passive"))
      (node (ref "SW0") (pin "3") (pinfunction "3_3") (pintype "passive"))
      (node (ref "SW0") (pin "4") (pinfunction "4_4") (pintype "passive"))
    )
    (net (code "30") (name "Net-(R2-Pad1)") (class "Default")
      (node (ref "R2") (pin "1") (pinfunction "1_1") (pintype "passive"))
      (node (ref "R6") (pin "1") (pinfunction "1_1") (pintype "passive"))
      (node (ref "SW1") (pin "3") (pinfunction "3_3") (pintype "passive"))
      (node (ref "SW1") (pin "4") (pinfunction "4_4") (pintype "passive"))
    )
    (net (code "31") (name "Net-(R3-Pad1)") (class "Default")
      (node (ref "R3") (pin "1") (pinfunction "1_1") (pintype "passive"))
      (node (ref "R7") (pin "1") (pinfunction "1_1") (pintype "passive"))
      (node (ref "SW2") (pin "3") (pinfunction "3_3") (pintype "passive"))
      (node (ref "SW2") (pin "4") (pinfunction "4_4") (pintype "passive"))
    )
    (net (code "32") (name "Net-(R4-Pad1)") (class "Default")
      (node (ref "R4") (pin "1") (pinfunction "1_1") (pintype "passive"))
      (node (ref "R8") (pin "1") (pinfunction "1_1") (pintype "passive"))
      (node (ref "SW3") (pin "3") (pinfunction "3_3") (pintype "passive"))
      (node (ref "SW3") (pin "4") (pinfunction "4_4") (pintype "passive"))
    )
    (net (code "33") (name "Net-(R10-Pad1)") (class "Default")
      (node (ref "R10") (pin "1") (pinfunction "1_1") (pintype "passive"))
      (node (ref "R14") (pin "1") (pinfunction "1_1") (pintype "passive"))
      (node (ref "SW5") (pin "3") (pinfunction "3_3") (pintype "passive"))
      (node (ref "SW5") (pin "4") (pinfunction "4_4") (pintype "passive"))
    )
    (net (code "34") (name "Net-(R11-Pad1)") (class "Default")
      (node (ref "R11") (pin "1") (pinfunction "1_1") (pintype "passive"))
      (node (ref "R15") (pin "1") (pinfunction "1_1") (pintype "passive"))
      (node (ref "SW6") (pin "3") (pinfunction "3_3") (pintype "passive"))
      (node (ref "SW6") (pin "4") (pinfunction "4_4") (pintype "passive"))
    )
    (net (code "35") (name "Net-(R12-Pad1)") (class "Default")
      (node (ref "R12") (pin "1") (pinfunction "1_1") (pintype "passive"))
      (node (ref "R16") (pin "1") (pinfunction "1_1") (pintype "passive"))
      (node (ref "SW7") (pin "3") (pinfunction "3_3") (pintype "passive"))
      (node (ref "SW7") (pin "4") (pinfunction "4_4") (pintype "passive"))
    )
    (net (code "36") (name "Net-(R13-Pad1)") (class "Default")
      (node (ref "R13") (pin "1") (pinfunction "1_1") (pintype "passive"))
      (node (ref "R9") (pin "1") (pinfunction "1_1") (pintype "passive"))
      (node (ref "SW4") (pin "3") (pinfunction "3_3") (pintype "passive"))
      (node (ref "SW4") (pin "4") (pinfunction "4_4") (pintype "passive"))
    )
    (net (code "37") (name "Net-(R17-Pad1)") (class "Default")
      (node (ref "R17") (pin "1") (pinfunction "1_1") (pintype "passive"))
      (node (ref "R20") (pin "1") (pinfunction "1_1") (pintype "passive"))
      (node (ref "SW13") (pin "3") (pinfunction "3_3") (pintype "passive"))
      (node (ref "SW13") (pin "4") (pinfunction "4_4") (pintype "passive"))
    )
    (net (code "38") (name "Net-(R18-Pad1)") (class "Default")
      (node (ref "R18") (pin "1") (pinfunction "1_1") (pintype "passive"))
      (node (ref "R21") (pin "1") (pinfunction "1_1") (pintype "passive"))
      (node (ref "SW14") (pin "3") (pinfunction "3_3") (pintype "passive"))
      (node (ref "SW14") (pin "4") (pinfunction "4_4") (pintype "passive"))
    )
    (net (code "39") (name "Net-(R19-Pad1)") (class "Default")
      (node (ref "R19") (pin "1") (pinfunction "1_1") (pintype "passive"))
      (node (ref "R22") (pin "1") (pinfunction "1_1") (pintype "passive"))
      (node (ref "SW15") (pin "3") (pinfunction "3_3") (pintype "passive"))
      (node (ref "SW15") (pin "4") (pinfunction "4_4") (pintype "passive"))
    )
    (net (code "40") (name "Net-(R31-Pad1)") (class "Default")
      (node (ref "R31") (pin "1") (pinfunction "1_1") (pintype "passive"))
      (node (ref "R36") (pin "1") (pinfunction "1_1") (pintype "passive"))
      (node (ref "SW8") (pin "3") (pinfunction "3_3") (pintype "passive"))
      (node (ref "SW8") (pin "4") (pinfunction "4_4") (pintype "passive"))
    )
    (net (code "41") (name "Net-(R32-Pad1)") (class "Default")
      (node (ref "R32") (pin "1") (pinfunction "1_1") (pintype "passive"))
      (node (ref "R37") (pin "1") (pinfunction "1_1") (pintype "passive"))
      (node (ref "SW9") (pin "3") (pinfunction "3_3") (pintype "passive"))
      (node (ref "SW9") (pin "4") (pinfunction "4_4") (pintype "passive"))
    )
    (net (code "42") (name "Net-(R33-Pad1)") (class "Default")
      (node (ref "R33") (pin "1") (pinfunction "1_1") (pintype "passive"))
      (node (ref "R38") (pin "1") (pinfunction "1_1") (pintype "passive"))
      (node (ref "SW10") (pin "3") (pinfunction "3_3") (pintype "passive"))
      (node (ref "SW10") (pin "4") (pinfunction "4_4") (pintype "passive"))
    )
    (net (code "43") (name "Net-(R34-Pad1)") (class "Default")
      (node (ref "R34") (pin "1") (pinfunction "1_1") (pintype "passive"))
      (node (ref "R39") (pin "1") (pinfunction "1_1") (pintype "passive"))
      (node (ref "SW11") (pin "3") (pinfunction "3_3") (pintype "passive"))
      (node (ref "SW11") (pin "4") (pinfunction "4_4") (pintype "passive"))
    )
    (net (code "44") (name "Net-(R35-Pad1)") (class "Default")
      (node (ref "R35") (pin "1") (pinfunction "1_1") (pintype "passive"))
      (node (ref "R40") (pin "1") (pinfunction "1_1") (pintype "passive"))
      (node (ref "SW12") (pin "3") (pinfunction "3_3") (pintype "passive"))
      (node (ref "SW12") (pin "4") (pinfunction "4_4") (pintype "passive"))
    )
    (net (code "45") (name "Net-(U1A-A)") (class "Default")
      (node (ref "C1") (pin "2") (pinfunction "2_2") (pintype "passive"))
      (node (ref "R5") (pin "2") (pinfunction "2_2") (pintype "passive"))
      (node (ref "U1") (pin "1") (pinfunction "A_1") (pintype "input"))
    )
    (net (code "46") (name "Net-(U1A-Y)") (class "Default")
      (node (ref "U1") (pin "2") (pinfunction "Y_2") (pintype "output"))
      (node (ref "U2") (pin "2") (pinfunction "CLK_2") (pintype "input"))
    )
    (net (code "47") (name "Net-(U1B-A)") (class "Default")
      (node (ref "C2") (pin "2") (pinfunction "2_2") (pintype "passive"))
      (node (ref "R6") (pin "2") (pinfunction "2_2") (pintype "passive"))
      (node (ref "U1") (pin "3") (pinfunction "A_3") (pintype "input"))
    )
    (net (code "48") (name "Net-(U1B-Y)") (class "Default")
      (node (ref "U1") (pin "4") (pinfunction "Y_4") (pintype "output"))
      (node (ref "U3") (pin "2") (pinfunction "CLK_2") (pintype "input"))
    )
    (net (code "49") (name "Net-(U1C-A)") (class "Default")
      (node (ref "C3") (pin "2") (pinfunction "2_2") (pintype "passive"))
      (node (ref "R7") (pin "2") (pinfunction "2_2") (pintype "passive"))
      (node (ref "U1") (pin "5") (pinfunction "A_5") (pintype "input"))
    )
    (net (code "50") (name "Net-(U1C-Y)") (class "Default")
      (node (ref "U1") (pin "6") (pinfunction "Y_6") (pintype "output"))
      (node (ref "U4") (pin "2") (pinfunction "CLK_2") (pintype "input"))
    )
    (net (code "51") (name "Net-(U1D-A)") (class "Default")
      (node (ref "C4") (pin "2") (pinfunction "2_2") (pintype "passive"))
      (node (ref "R8") (pin "2") (pinfunction "2_2") (pintype "passive"))
      (node (ref "U1") (pin "9") (pinfunction "A_9") (pintype "input"))
    )
    (net (code "52") (name "Net-(U1D-Y)") (class "Default")
      (node (ref "U1") (pin "8") (pinfunction "Y_8") (pintype "output"))
      (node (ref "U5") (pin "2") (pinfunction "CLK_2") (pintype "input"))
    )
    (net (code "53") (name "Net-(U6A-A)") (class "Default")
      (node (ref "C5") (pin "2") (pinfunction "2_2") (pintype "passive"))
      (node (ref "R13") (pin "2") (pinfunction "2_2") (pintype "passive"))
      (node (ref "U6") (pin "1") (pinfunction "A_1") (pintype "input"))
    )
    (net (code "54") (name "Net-(U6A-Y)") (class "Default")
      (node (ref "U6") (pin "2") (pinfunction "Y_2") (pintype "output"))
      (node (ref "U7") (pin "2") (pinfunction "CLK_2") (pintype "input"))
    )
    (net (code "55") (name "Net-(U6B-A)") (class "Default")
      (node (ref "C6") (pin "2") (pinfunction "2_2") (pintype "passive"))
      (node (ref "R14") (pin "2") (pinfunction "2_2") (pintype "passive"))
      (node (ref "U6") (pin "3") (pinfunction "A_3") (pintype "input"))
    )
    (net (code "56") (name "Net-(U6B-Y)") (class "Default")
      (node (ref "U6") (pin "4") (pinfunction "Y_4") (pintype "output"))
      (node (ref "U8") (pin "2") (pinfunction "CLK_2") (pintype "input"))
    )
    (net (code "57") (name "Net-(U6C-A)") (class "Default")
      (node (ref "C7") (pin "2") (pinfunction "2_2") (pintype "passive"))
      (node (ref "R15") (pin "2") (pinfunction "2_2") (pintype "passive"))
      (node (ref "U6") (pin "5") (pinfunction "A_5") (pintype "input"))
    )
    (net (code "58") (name "Net-(U6C-Y)") (class "Default")
      (node (ref "U6") (pin "6") (pinfunction "Y_6") (pintype "output"))
      (node (ref "U9") (pin "2") (pinfunction "CLK_2") (pintype "input"))
    )
    (net (code "59") (name "Net-(U6D-A)") (class "Default")
      (node (ref "C8") (pin "2") (pinfunction "2_2") (pintype "passive"))
      (node (ref "R16") (pin "2") (pinfunction "2_2") (pintype "passive"))
      (node (ref "U6") (pin "9") (pinfunction "A_9") (pintype "input"))
    )
    (net (code "60") (name "Net-(U10-CLK)") (class "Default")
      (node (ref "U10") (pin "2") (pinfunction "CLK_2") (pintype "input"))
      (node (ref "U6") (pin "8") (pinfunction "Y_8") (pintype "output"))
    )
    (net (code "61") (name "Net-(U11-CLK)") (class "Default")
      (node (ref "U11") (pin "2") (pinfunction "CLK_2") (pintype "input"))
      (node (ref "U23") (pin "2") (pinfunction "Y_2") (pintype "output"))
    )
    (net (code "62") (name "Net-(U12-CLK)") (class "Default")
      (node (ref "U12") (pin "2") (pinfunction "CLK_2") (pintype "input"))
      (node (ref "U23") (pin "4") (pinfunction "Y_4") (pintype "output"))
    )
    (net (code "63") (name "Net-(U13-CLK)") (class "Default")
      (node (ref "U13") (pin "2") (pinfunction "CLK_2") (pintype "input"))
      (node (ref "U23") (pin "6") (pinfunction "Y_6") (pintype "output"))
    )
    (net (code "64") (name "Net-(U14A-A)") (class "Default")
      (node (ref "C12") (pin "2") (pinfunction "2_2") (pintype "passive"))
      (node (ref "R36") (pin "2") (pinfunction "2_2") (pintype "passive"))
      (node (ref "U14") (pin "1") (pinfunction "A_1") (pintype "input"))
    )
    (net (code "65") (name "Net-(U14B-A)") (class "Default")
      (node (ref "C13") (pin "2") (pinfunction "2_2") (pintype "passive"))
      (node (ref "R37") (pin "2") (pinfunction "2_2") (pintype "passive"))
      (node (ref "U14") (pin "3") (pinfunction "A_3") (pintype "input"))
    )
    (net (code "66") (name "Net-(U14C-A)") (class "Default")
      (node (ref "C14") (pin "2") (pinfunction "2_2") (pintype "passive"))
      (node (ref "R38") (pin "2") (pinfunction "2_2") (pintype "passive"))
      (node (ref "U14") (pin "5") (pinfunction "A_5") (pintype "input"))
    )
    (net (code "67") (name "Net-(U14D-A)") (class "Default")
      (node (ref "C15") (pin "2") (pinfunction "2_2") (pintype "passive"))
      (node (ref "R39") (pin "2") (pinfunction "2_2") (pintype "passive"))
      (node (ref "U14") (pin "9") (pinfunction "A_9") (pintype "input"))
    )
    (net (code "68") (name "Net-(U14E-A)") (class "Default")
      (node (ref "C16") (pin "2") (pinfunction "2_2") (pintype "passive"))
      (node (ref "R40") (pin "2") (pinfunction "2_2") (pintype "passive"))
      (node (ref "U14") (pin "11") (pinfunction "A_11") (pintype "input"))
    )
    (net (code "69") (name "Net-(U23A-A)") (class "Default")
      (node (ref "C9") (pin "2") (pinfunction "2_2") (pintype "passive"))
      (node (ref "R20") (pin "2") (pinfunction "2_2") (pintype "passive"))
      (node (ref "U23") (pin "1") (pinfunction "A_1") (pintype "input"))
    )
    (net (code "70") (name "Net-(U23B-A)") (class "Default")
      (node (ref "C10") (pin "2") (pinfunction "2_2") (pintype "passive"))
      (node (ref "R21") (pin "2") (pinfunction "2_2") (pintype "passive"))
      (node (ref "U23") (pin "3") (pinfunction "A_3") (pintype "input"))
    )
    (net (code "71") (name "Net-(U23C-A)") (class "Default")
      (node (ref "C11") (pin "2") (pinfunction "2_2") (pintype "passive"))
      (node (ref "R22") (pin "2") (pinfunction "2_2") (pintype "passive"))
      (node (ref "U23") (pin "5") (pinfunction "A_5") (pintype "input"))
    )
    (net (code "72") (name "VCC") (class "Default")
      (node (ref "C20") (pin "2") (pinfunction "2_2") (pintype "passive"))
      (node (ref "C21") (pin "2") (pinfunction "2_2") (pintype "passive"))
      (node (ref "C22") (pin "2") (pinfunction "2_2") (pintype "passive"))
      (node (ref "C23") (pin "2") (pinfunction "2_2") (pintype "passive"))
      (node (ref "C24") (pin "2") (pinfunction "2_2") (pintype "passive"))
      (node (ref "C25") (pin "2") (pinfunction "2_2") (pintype "passive"))
      (node (ref "C26") (pin "2") (pinfunction "2_2") (pintype "passive"))
      (node (ref "C27") (pin "2") (pinfunction "2_2") (pintype "passive"))
      (node (ref "C28") (pin "2") (pinfunction "2_2") (pintype "passive"))
      (node (ref "C29") (pin "2") (pinfunction "2_2") (pintype "passive"))
      (node (ref "C30") (pin "2") (pinfunction "2_2") (pintype "passive"))
      (node (ref "C31") (pin "1") (pinfunction "1_1") (pintype "passive"))
      (node (ref "C32") (pin "1") (pinfunction "1_1") (pintype "passive"))
      (node (ref "R1") (pin "2") (pinfunction "2_2") (pintype "passive"))
      (node (ref "R10") (pin "2") (pinfunction "2_2") (pintype "passive"))
      (node (ref "R11") (pin "2") (pinfunction "2_2") (pintype "passive"))
      (node (ref "R12") (pin "2") (pinfunction "2_2") (pintype "passive"))
      (node (ref "R17") (pin "2") (pinfunction "2_2") (pintype "passive"))
      (node (ref "R18") (pin "2") (pinfunction "2_2") (pintype "passive"))
      (node (ref "R19") (pin "2") (pinfunction "2_2") (pintype "passive"))
      (node (ref "R2") (pin "2") (pinfunction "2_2") (pintype "passive"))
      (node (ref "R3") (pin "2") (pinfunction "2_2") (pintype "passive"))
      (node (ref "R31") (pin "2") (pinfunction "2_2") (pintype "passive"))
      (node (ref "R32") (pin "2") (pinfunction "2_2") (pintype "passive"))
      (node (ref "R33") (pin "2") (pinfunction "2_2") (pintype "passive"))
      (node (ref "R34") (pin "2") (pinfunction "2_2") (pintype "passive"))
      (node (ref "R35") (pin "2") (pinfunction "2_2") (pintype "passive"))
      (node (ref "R4") (pin "2") (pinfunction "2_2") (pintype "passive"))
      (node (ref "R9") (pin "2") (pinfunction "2_2") (pintype "passive"))
      (node (ref "U1") (pin "14") (pinfunction "VCC_14") (pintype "power_in"))
      (node (ref "U10") (pin "5") (pinfunction "VCC_5") (pintype "power_in"))
      (node (ref "U11") (pin "5") (pinfunction "VCC_5") (pintype "power_in"))
      (node (ref "U12") (pin "5") (pinfunction "VCC_5") (pintype "power_in"))
      (node (ref "U13") (pin "5") (pinfunction "VCC_5") (pintype "power_in"))
      (node (ref "U14") (pin "14") (pinfunction "VCC_14") (pintype "power_in"))
      (node (ref "U2") (pin "5") (pinfunction "VCC_5") (pintype "power_in"))
      (node (ref "U23") (pin "14") (pinfunction "VCC_14") (pintype "power_in"))
      (node (ref "U28") (pin "3") (pinfunction "VOUT_3") (pintype "power_in"))
      (node (ref "U3") (pin "5") (pinfunction "VCC_5") (pintype "power_in"))
      (node (ref "U4") (pin "5") (pinfunction "VCC_5") (pintype "power_in"))
      (node (ref "U5") (pin "5") (pinfunction "VCC_5") (pintype "power_in"))
      (node (ref "U6") (pin "14") (pinfunction "VCC_14") (pintype "power_in"))
      (node (ref "U7") (pin "5") (pinfunction "VCC_5") (pintype "power_in"))
      (node (ref "U8") (pin "5") (pinfunction "VCC_5") (pintype "power_in"))
      (node (ref "U9") (pin "5") (pinfunction "VCC_5") (pintype "power_in"))
    )
    (net (code "73") (name "unconnected-(J1-Pad3)") (class "Default")
      (node (ref "J1") (pin "3") (pinfunction "3_3") (pintype "power_in"))
    )
    (net (code "74") (name "unconnected-(U1E-Y-Pad10)") (class "Default")
      (node (ref "U1") (pin "10") (pinfunction "Y_10") (pintype "output"))
    )
    (net (code "75") (name "unconnected-(U1F-Y-Pad12)") (class "Default")
      (node (ref "U1") (pin "12") (pinfunction "Y_12") (pintype "output"))
    )
    (net (code "76") (name "unconnected-(U6E-Y-Pad10)") (class "Default")
      (node (ref "U6") (pin "10") (pinfunction "Y_10") (pintype "output"))
    )
    (net (code "77") (name "unconnected-(U6F-Y-Pad12)") (class "Default")
      (node (ref "U6") (pin "12") (pinfunction "Y_12") (pintype "output"))
    )
    (net (code "78") (name "unconnected-(U14F-Y-Pad12)") (class "Default")
      (node (ref "U14") (pin "12") (pinfunction "Y_12") (pintype "output"))
    )
  )
)
